# 5_RS485.net
KiCad netlist of a schematic drawn in Altium Designer
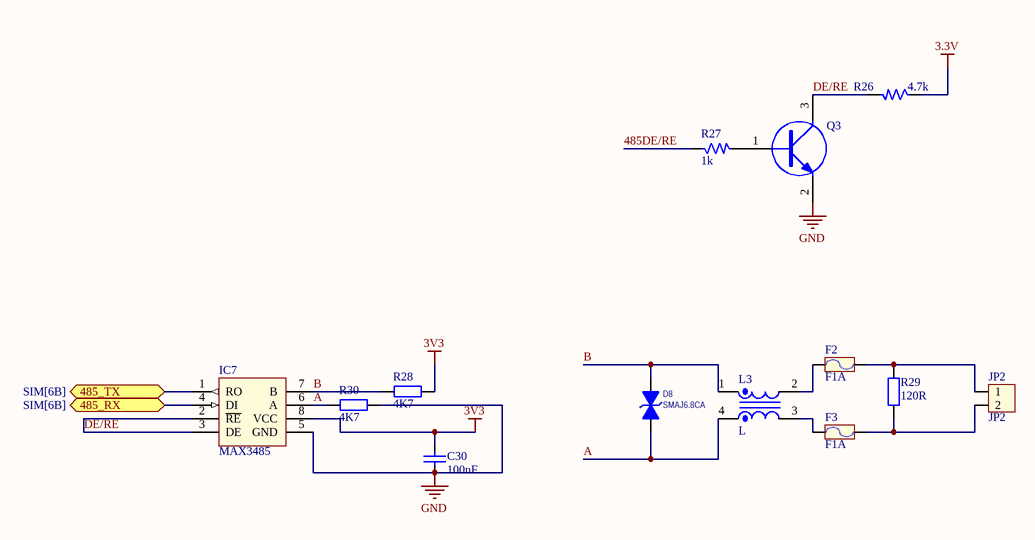
[diagram p0: 5.RS485.SchDoc]

(export (version "E")
  (design (tool "Eeschema 10.0.6"))
  (components
    (comp (ref "C30")
      (value "100nF")
      (footprint "CAP_0402")
      (description "Capacitor")
      (fields (field (name "PUBLISHER") "Altium Limited"))
      (libsource (lib "Main") (part "CapSMD"))
    )
    (comp (ref "D8")
      (value "SMAJ6.8CA")
      (footprint "SOD323 - DO241")
      (description "TVS DIODE 30VWM 48.4VC SMA")
      (fields (field (name "MANUFACTURER") "Bourns Inc.") (field (name "PART NUMBER") "PSD12C"))
      (libsource (lib "Anh_Trung") (part "SMAJ30CA-30V/8.3A"))
    )
    (comp (ref "F2")
      (value "F1A")
      (footprint "RES-SMD-1206")
      (description "F smd1206 0.315A")
      (fields (field (name "DESIGNED BY") "VanDungEvn"))
      (libsource (lib "Main") (part "Fuse"))
    )
    (comp (ref "F3")
      (value "F1A")
      (footprint "RES-SMD-1206")
      (description "F smd1206 0.315A")
      (fields (field (name "DESIGNED BY") "VanDungEvn"))
      (libsource (lib "Main") (part "Fuse"))
    )
    (comp (ref "IC7")
      (value "MAX3485")
      (footprint "SOIC-8")
      (description "IC TRANSCEIVER HALF 1/1 SOT23-8")
      (fields (field (name "MANUFACTURER") "Maxim Integrated") (field (name "PART NUMBER") "MAX3362EKA+T"))
      (libsource (lib "Anh_Trung") (part "MAX3362EKA+T"))
    )
    (comp (ref "JP2")
      (value "JP2")
      (footprint "KF2-5.08")
      (description "Connector 2")
      (libsource (lib "Anh_Trung") (part "Con2"))
    )
    (comp (ref "L3")
      (value "L")
      (footprint "Anh_Trung:L-B82793S0513N201")
      (description "CMC 51UH 800MA 2LN SMD AEC-Q200")
      (fields
        (field (name "MANUFACTURER") "EPCOS - TDK Electronics")
        (field (name "PART NUMBER") "B82793S0513N201")
      )
      (libsource (lib "Anh_Trung") (part "L filter Common Mode Chokes"))
    )
    (comp (ref "Q3")
      (value "C1815(MMBT4401)")
      (footprint "SOT23")
      (description "Transistor C1815, SOT23")
      (fields (field (name "MANUFACTURER") "Fairchild Semiconductor") (field (name "PART NUMBER") "MMBT4401"))
      (libsource (lib "Anh_Trung") (part "NPN"))
    )
    (comp (ref "R26")
      (value "4.7k")
      (footprint "R-0805")
      (description "RES SMD 4.7K OHM 1% 1/8W 0805")
      (fields (field (name "MANUFACTURER") "Yageo") (field (name "PART NUMBER") "RC0805FR-074K7L"))
      (libsource (lib "Anh_Trung") (part "R"))
    )
    (comp (ref "R27")
      (value "1k")
      (footprint "R-0805")
      (description "Resistor 1/4W")
      (fields (field (name "MANUFACTURER") "Yageo") (field (name "PART NUMBER") "RC0805FR-071KL"))
      (libsource (lib "Anh_Trung") (part "R"))
    )
    (comp (ref "R28")
      (value "4K7")
      (footprint "RES-SMD-0805")
      (description "Resistor SMD")
      (fields
        (field (name "MANUFACTURER") "Generic Components")
        (field (name "PUBLISHER") "Altium Hobart Technology Centre")
      )
      (libsource (lib "Main") (part "Resistor - SMD"))
    )
    (comp (ref "R29")
      (value "120R")
      (footprint "RES-SMD-0805")
      (description "Resistor SMD")
      (fields
        (field (name "MANUFACTURER") "Generic Components")
        (field (name "PUBLISHER") "Altium Hobart Technology Centre")
      )
      (libsource (lib "Main") (part "Resistor - SMD"))
    )
    (comp (ref "R30")
      (value "4K7")
      (footprint "RES-SMD-0805")
      (description "Resistor SMD")
      (fields
        (field (name "MANUFACTURER") "Generic Components")
        (field (name "PUBLISHER") "Altium Hobart Technology Centre")
      )
      (libsource (lib "Main") (part "Resistor - SMD"))
    )
  )
  (nets
    (net (code "1") (name "/485DE{slash}RE") (class "Default")
      (node (ref "R27") (pin "1") (pinfunction "1_1") (pintype "passive"))
    )
    (net (code "2") (name "/485_RX") (class "Default")
      (node (ref "IC7") (pin "4") (pinfunction "DI_4") (pintype "input"))
    )
    (net (code "3") (name "/485_TX") (class "Default")
      (node (ref "IC7") (pin "1") (pinfunction "RO_1") (pintype "output"))
    )
    (net (code "4") (name "/A") (class "Default")
      (node (ref "D8") (pin "1") (pinfunction "A_1") (pintype "passive"))
      (node (ref "IC7") (pin "6") (pinfunction "A_6") (pintype "passive"))
      (node (ref "L3") (pin "4") (pintype "passive"))
      (node (ref "R30") (pin "1") (pinfunction "1_1") (pintype "passive"))
    )
    (net (code "5") (name "/B") (class "Default")
      (node (ref "D8") (pin "2") (pinfunction "K_2") (pintype "passive"))
      (node (ref "IC7") (pin "7") (pinfunction "B_7") (pintype "passive"))
      (node (ref "L3") (pin "1") (pintype "passive"))
      (node (ref "R28") (pin "1") (pinfunction "1_1") (pintype "passive"))
    )
    (net (code "6") (name "/DE{slash}RE") (class "Default")
      (node (ref "IC7") (pin "2") (pinfunction "~{RE}_2") (pintype "passive"))
      (node (ref "IC7") (pin "3") (pinfunction "DE_3") (pintype "passive"))
      (node (ref "Q3") (pin "3") (pinfunction "C_3") (pintype "passive"))
      (node (ref "R26") (pin "2") (pinfunction "2_2") (pintype "passive"))
    )
    (net (code "7") (name "3.3V") (class "Default")
      (node (ref "R26") (pin "1") (pinfunction "1_1") (pintype "passive"))
    )
    (net (code "8") (name "3V3") (class "Default")
      (node (ref "C30") (pin "1") (pinfunction "1_1") (pintype "passive"))
      (node (ref "IC7") (pin "8") (pinfunction "VCC_8") (pintype "passive"))
      (node (ref "R28") (pin "2") (pinfunction "2_2") (pintype "passive"))
    )
    (net (code "9") (name "GND") (class "Default")
      (node (ref "C30") (pin "2") (pinfunction "2_2") (pintype "passive"))
      (node (ref "IC7") (pin "5") (pinfunction "GND_5") (pintype "passive"))
      (node (ref "Q3") (pin "2") (pinfunction "E_2") (pintype "passive"))
      (node (ref "R30") (pin "2") (pinfunction "2_2") (pintype "passive"))
    )
    (net (code "10") (name "Net-(F2-Pad1)") (class "Default")
      (node (ref "F2") (pin "1") (pinfunction "1_1") (pintype "passive"))
      (node (ref "L3") (pin "2") (pintype "passive"))
    )
    (net (code "11") (name "Net-(F2-Pad2)") (class "Default")
      (node (ref "F2") (pin "2") (pinfunction "2_2") (pintype "passive"))
      (node (ref "JP2") (pin "1") (pinfunction "1_1") (pintype "passive"))
      (node (ref "R29") (pin "1") (pinfunction "1_1") (pintype "passive"))
    )
    (net (code "12") (name "Net-(F3-Pad1)") (class "Default")
      (node (ref "F3") (pin "1") (pinfunction "1_1") (pintype "passive"))
      (node (ref "L3") (pin "3") (pintype "passive"))
    )
    (net (code "13") (name "Net-(F3-Pad2)") (class "Default")
      (node (ref "F3") (pin "2") (pinfunction "2_2") (pintype "passive"))
      (node (ref "JP2") (pin "2") (pinfunction "2_2") (pintype "passive"))
      (node (ref "R29") (pin "2") (pinfunction "2_2") (pintype "passive"))
    )
    (net (code "14") (name "Net-(Q3-B)") (class "Default")
      (node (ref "Q3") (pin "1") (pinfunction "B_1") (pintype "passive"))
      (node (ref "R27") (pin "2") (pinfunction "2_2") (pintype "passive"))
    )
  )
)
